# Regulators.net
KiCad netlist of a schematic drawn in Altium Designer
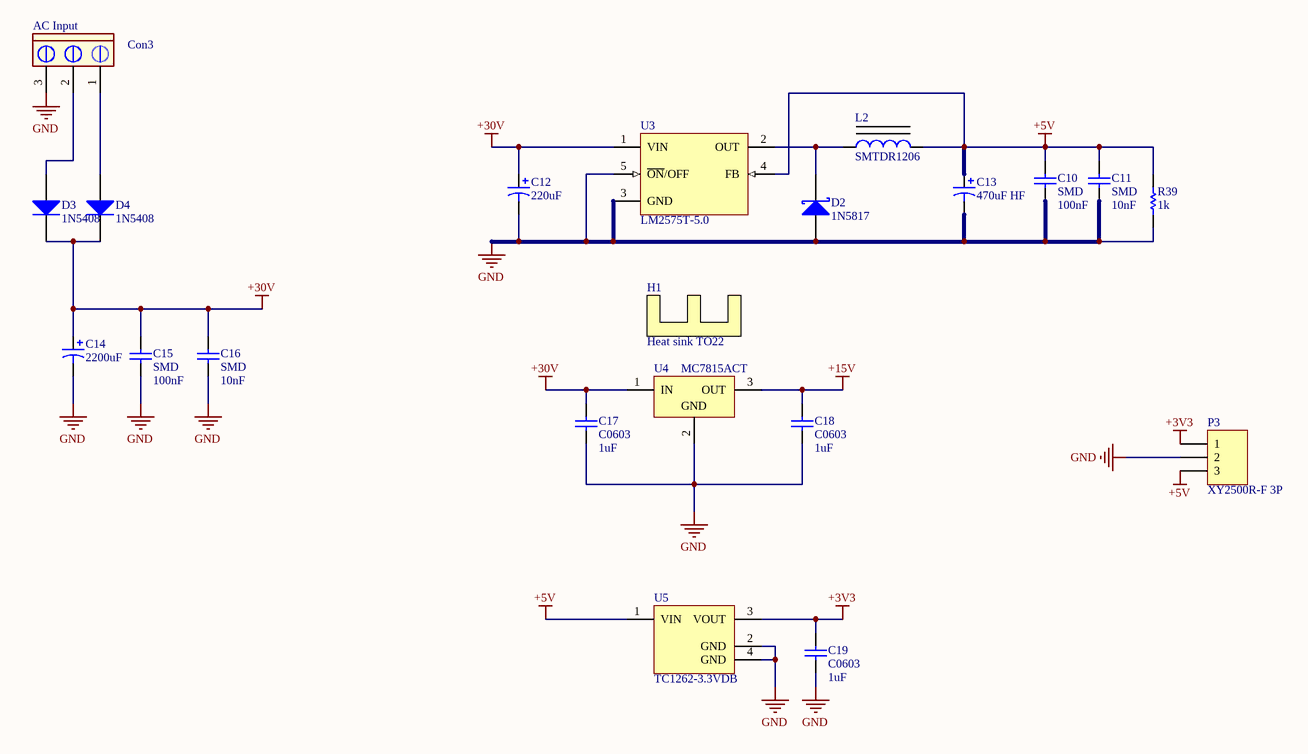
[diagram p0: Regulators.SchDoc]

(export (version "E")
  (design (tool "Eeschema 10.0.6"))
  (components
    (comp (ref "C10")
      (value "SMD")
      (footprint "1206")
      (description "Ceramic Chip Capacitor - Standard")
      (fields (field (name "ALTIUM_VALUE") "100nF") (field (name "PUBLISHER") "Altium Limited"))
      (libsource (lib "KEMET Chip Capacitor") (part "C1206"))
    )
    (comp (ref "C11")
      (value "SMD")
      (footprint "1206")
      (description "Ceramic Chip Capacitor - Standard")
      (fields (field (name "ALTIUM_VALUE") "10nF") (field (name "PUBLISHER") "Altium Limited"))
      (libsource (lib "KEMET Chip Capacitor") (part "C1206"))
    )
    (comp (ref "C12")
      (value "220uF")
      (footprint "CAPPR5-10X16")
      (description "Aluminum Electrolytic Capacitor, Radial Style with Long Leads: 220uF, 63V")
      (fields (field (name "PUBLISHER") "Altium Limited"))
      (libsource (lib "Vishay Roederstein Electrolytic Radial-Lead Capacitor") (part "EKA00DD322J00"))
    )
    (comp (ref "C13")
      (value "470uF HF")
      (footprint "CAPPR5-10X20")
      (description "Aluminum Electrolytic Capacitor, Radial Style with Long Leads: 470uF, 25V")
      (fields (field (name "PUBLISHER") "Altium Limited"))
      (libsource (lib "Vishay Roederstein Electrolytic Radial-Lead Capacitor") (part "EKC00DE347E00"))
    )
    (comp (ref "C14")
      (value "2200uF")
      (footprint "CAPPR7.5-16X35.5")
      (description "Aluminum Electrolytic Capacitor, Radial Style with Long Leads: 2200uF, 50V")
      (fields (field (name "PUBLISHER") "Altium Limited"))
      (libsource (lib "Vishay Roederstein Electrolytic Radial-Lead Capacitor") (part "EKA00JL422H00"))
    )
    (comp (ref "C15")
      (value "SMD")
      (footprint "1206")
      (description "Ceramic Chip Capacitor - Standard")
      (fields (field (name "ALTIUM_VALUE") "100nF") (field (name "PUBLISHER") "Altium Limited"))
      (libsource (lib "KEMET Chip Capacitor") (part "C1206"))
    )
    (comp (ref "C16")
      (value "SMD")
      (footprint "1206")
      (description "Ceramic Chip Capacitor - Standard")
      (fields (field (name "ALTIUM_VALUE") "10nF") (field (name "PUBLISHER") "Altium Limited"))
      (libsource (lib "KEMET Chip Capacitor") (part "C1206"))
    )
    (comp (ref "C17")
      (value "C0603")
      (footprint "0603")
      (description "C1608X7R1C105K X7R")
      (fields (field (name "ALTIUM_VALUE") "1uF") (field (name "PUBLISHER") "Altium Limited"))
      (libsource (lib "KEMET Chip Capacitor") (part "C0603"))
    )
    (comp (ref "C18")
      (value "C0603")
      (footprint "0603")
      (description "C1608X7R1C105K X7R")
      (fields (field (name "ALTIUM_VALUE") "1uF") (field (name "PUBLISHER") "Altium Limited"))
      (libsource (lib "KEMET Chip Capacitor") (part "C0603"))
    )
    (comp (ref "C19")
      (value "C0603")
      (footprint "0603")
      (description "C1608X7R1C105K X7R")
      (fields (field (name "ALTIUM_VALUE") "1uF") (field (name "PUBLISHER") "Altium Limited"))
      (libsource (lib "KEMET Chip Capacitor") (part "C0603"))
    )
    (comp (ref "Con3")
      (value "AC Input")
      (footprint "My_CN3")
      (description "Connector green screw")
      (libsource (lib "Mylib") (part "CON3 pin Green"))
    )
    (comp (ref "D2")
      (value "1N5817")
      (footprint "DO-41")
      (description "Schottky Rectifier")
      (fields (field (name "PUBLISHER") "Altium Limited"))
      (libsource (lib "IR Rectifier - Schottky") (part "1N6095"))
    )
    (comp (ref "D3")
      (value "1N5408")
      (footprint "DO-201AD")
      (description "3 Amp Medium Power Silicon Rectifier Diode")
      (fields (field (name "PUBLISHER") "Altium Limited"))
      (libsource (lib "Miscellaneous Devices") (part "Diode 1N5408"))
    )
    (comp (ref "D4")
      (value "1N5408")
      (footprint "DO-201AD")
      (description "3 Amp Medium Power Silicon Rectifier Diode")
      (fields (field (name "PUBLISHER") "Altium Limited"))
      (libsource (lib "Miscellaneous Devices") (part "Diode 1N5408"))
    )
    (comp (ref "H1")
      (value "Heat sink TO22")
      (footprint "My_Heat_sink_TO22")
      (description "Heat sink for TO22")
      (libsource (lib "Mylib") (part "Heat sink TO22"))
    )
    (comp (ref "L2")
      (value "SMTDR1206")
      (footprint "SMTDR1206 Inductor")
      (description "100UHY SMD 18.54X7.11MM 20% 3A 0.19E SMTDR1206-101M")
      (libsource (lib "NXT - Inductors") (part "100UHY SMD 18.54X7.11MM 20% 3A 0.19E SMTDR1206-101M"))
    )
    (comp (ref "P3")
      (value "XY2500R-F 3P")
      (footprint "XY2500R-F 3P")
      (description "HEADER 3P P/CI 90gra VERDE P=3.81MM XY2500R-F")
      (libsource (lib "NXT - Connectors") (part "XY2500R-F 3P"))
    )
    (comp (ref "R39")
      (value "1k")
      (footprint "8RB-1206")
      (fields (field (name "Comment") "SMD") (field (name "PUBLISHER") "Altium Limited"))
      (libsource (lib "Panasonic Resistor") (part "ERJ8BQ"))
    )
    (comp (ref "U3")
      (value "LM2575T-5.0")
      (footprint "T05A")
      (description "SIMPLE SWITCHER® 1A Step-Down Voltage Regulator, 5-pin TO-220")
      (fields
        (field (name "MANUFACTURER") "National Semiconductor")
        (field (name "PUBLISHER") "Altium Limited")
      )
      (libsource (lib "NSC Switcher") (part "LM2575T-5.0"))
    )
    (comp (ref "U4")
      (value "MC7815ACT")
      (footprint "221A-04")
      (description "3-Terminal Positive Fixed Voltage Regulator")
      (fields (field (name "PUBLISHER") "Altium Limited"))
      (libsource (lib "Motorola Power Mgt Voltage Regulator") (part "MC7815ACT"))
    )
    (comp (ref "U5")
      (value "TC1262-3.3VDB")
      (footprint "SOT-223-DB3_N")
      (description "500mA Fixed Output CMOS LDO, 3-Pin SOT-223, Extended Temperature")
      (fields (field (name "PUBLISHER") "Altium Limited"))
      (libsource (lib "Microchip Power Mgt Line Regulator") (part "TC1262-3.3VDB"))
    )
  )
  (nets
    (net (code "1") (name "+3V3") (class "Default")
      (node (ref "C19") (pin "2") (pinfunction "2_2") (pintype "passive"))
      (node (ref "P3") (pin "1") (pinfunction "1_1") (pintype "passive"))
      (node (ref "U5") (pin "3") (pinfunction "VOUT_3") (pintype "power_in"))
    )
    (net (code "2") (name "+5V") (class "Default")
      (node (ref "C10") (pin "2") (pinfunction "2_2") (pintype "passive"))
      (node (ref "C11") (pin "2") (pinfunction "2_2") (pintype "passive"))
      (node (ref "C13") (pin "1") (pinfunction "1_1") (pintype "passive"))
      (node (ref "L2") (pin "2") (pinfunction "2_2") (pintype "passive"))
      (node (ref "P3") (pin "3") (pinfunction "3_3") (pintype "passive"))
      (node (ref "R39") (pin "2") (pinfunction "2_2") (pintype "passive"))
      (node (ref "U3") (pin "4") (pinfunction "FB_4") (pintype "input"))
      (node (ref "U5") (pin "1") (pinfunction "VIN_1") (pintype "power_in"))
    )
    (net (code "3") (name "+15V") (class "Default")
      (node (ref "C18") (pin "2") (pinfunction "2_2") (pintype "passive"))
      (node (ref "U4") (pin "3") (pinfunction "OUT_3") (pintype "power_in"))
    )
    (net (code "4") (name "+30V") (class "Default")
      (node (ref "C12") (pin "1") (pinfunction "1_1") (pintype "passive"))
      (node (ref "C14") (pin "1") (pinfunction "1_1") (pintype "passive"))
      (node (ref "C15") (pin "2") (pinfunction "2_2") (pintype "passive"))
      (node (ref "C16") (pin "2") (pinfunction "2_2") (pintype "passive"))
      (node (ref "C17") (pin "2") (pinfunction "2_2") (pintype "passive"))
      (node (ref "D3") (pin "2") (pinfunction "K_2") (pintype "passive"))
      (node (ref "D4") (pin "2") (pinfunction "K_2") (pintype "passive"))
      (node (ref "U3") (pin "1") (pinfunction "VIN_1") (pintype "power_in"))
      (node (ref "U4") (pin "1") (pinfunction "IN_1") (pintype "power_in"))
    )
    (net (code "5") (name "GND") (class "Default")
      (node (ref "C10") (pin "1") (pinfunction "1_1") (pintype "passive"))
      (node (ref "C11") (pin "1") (pinfunction "1_1") (pintype "passive"))
      (node (ref "C12") (pin "2") (pinfunction "2_2") (pintype "passive"))
      (node (ref "C13") (pin "2") (pinfunction "2_2") (pintype "passive"))
      (node (ref "C14") (pin "2") (pinfunction "2_2") (pintype "passive"))
      (node (ref "C15") (pin "1") (pinfunction "1_1") (pintype "passive"))
      (node (ref "C16") (pin "1") (pinfunction "1_1") (pintype "passive"))
      (node (ref "C17") (pin "1") (pinfunction "1_1") (pintype "passive"))
      (node (ref "C18") (pin "1") (pinfunction "1_1") (pintype "passive"))
      (node (ref "C19") (pin "1") (pinfunction "1_1") (pintype "passive"))
      (node (ref "Con3") (pin "3") (pinfunction "3_3") (pintype "passive"))
      (node (ref "D2") (pin "1") (pinfunction "A_1") (pintype "passive"))
      (node (ref "P3") (pin "2") (pinfunction "2_2") (pintype "passive"))
      (node (ref "R39") (pin "1") (pinfunction "1_1") (pintype "passive"))
      (node (ref "U3") (pin "3") (pinfunction "GND_3") (pintype "power_in"))
      (node (ref "U3") (pin "5") (pinfunction "~{ON}/OFF_5") (pintype "input"))
      (node (ref "U4") (pin "2") (pinfunction "GND_2") (pintype "power_in"))
      (node (ref "U5") (pin "2") (pinfunction "GND_2") (pintype "power_in"))
      (node (ref "U5") (pin "4") (pinfunction "GND_4") (pintype "power_in"))
    )
    (net (code "6") (name "Net-(D2-K)") (class "Default")
      (node (ref "D2") (pin "2") (pinfunction "K_2") (pintype "passive"))
      (node (ref "L2") (pin "1") (pinfunction "1_1") (pintype "passive"))
      (node (ref "U3") (pin "2") (pinfunction "OUT_2") (pintype "power_in"))
    )
    (net (code "7") (name "Net-(D3-A)") (class "Default")
      (node (ref "Con3") (pin "2") (pinfunction "2_2") (pintype "passive"))
      (node (ref "D3") (pin "1") (pinfunction "A_1") (pintype "passive"))
    )
    (net (code "8") (name "Net-(D4-A)") (class "Default")
      (node (ref "Con3") (pin "1") (pinfunction "1_1") (pintype "passive"))
      (node (ref "D4") (pin "1") (pinfunction "A_1") (pintype "passive"))
    )
  )
)
